# PC_PS2.net
KiCad netlist of a schematic drawn in Altium Designer
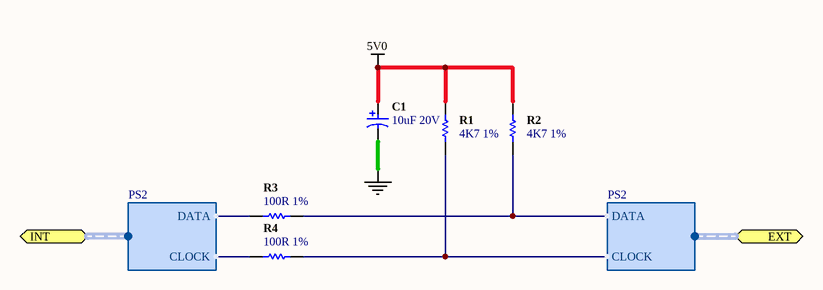
[diagram p0: PC_PS2.SchDoc]

(export (version "E")
  (design (tool "Eeschema 10.0.6"))
  (components
    (comp (ref "C1")
      (value "10uF 20V")
      (footprint "CAPC3528-STAR")
      (description "Capacitor, Tantalum, 10uF 10% 20V MCCT-B (3528)")
      (fields (field (name "TOLERANCE") "10 %"))
      (libsource (lib "altium-import") (part "root_0_CAP-P_"))
    )
    (comp (ref "R1")
      (value "4K7 1%")
      (footprint "RESC1005-STAR")
      (description "Resistor, 4K7 1% 0402 (1005)")
      (fields (field (name "TOLERANCE") "1 %"))
      (libsource (lib "altium-import") (part "root_0_RES_"))
    )
    (comp (ref "R2")
      (value "4K7 1%")
      (footprint "RESC1005-STAR")
      (description "Resistor, 4K7 1% 0402 (1005)")
      (fields (field (name "TOLERANCE") "1 %"))
      (libsource (lib "altium-import") (part "root_0_RES_"))
    )
    (comp (ref "R3")
      (value "100R 1%")
      (footprint "RESC1005-STAR")
      (description "Resistor, 100R 1% 0402 (1005)")
      (fields (field (name "TOLERANCE") "1 %"))
      (libsource (lib "altium-import") (part "root_1_RES_"))
    )
    (comp (ref "R4")
      (value "100R 1%")
      (footprint "RESC1005-STAR")
      (description "Resistor, 100R 1% 0402 (1005)")
      (fields (field (name "TOLERANCE") "1 %"))
      (libsource (lib "altium-import") (part "root_1_RES_"))
    )
  )
  (nets
    (net (code "3") (name "5V0") (class "Default")
      (node (ref "C1") (pin "1") (pinfunction "1_1") (pintype "passive"))
      (node (ref "R1") (pin "1") (pinfunction "1_1") (pintype "passive"))
      (node (ref "R2") (pin "1") (pinfunction "1_1") (pintype "passive"))
    )
    (net (code "4") (name "GND") (class "Default")
      (node (ref "C1") (pin "2") (pinfunction "2_2") (pintype "passive"))
    )
    (net (code "5") (name "Net-(R1-Pad2)") (class "Default")
      (node (ref "R1") (pin "2") (pinfunction "2_2") (pintype "passive"))
      (node (ref "R4") (pin "2") (pinfunction "2_2") (pintype "passive"))
    )
    (net (code "6") (name "Net-(R2-Pad2)") (class "Default")
      (node (ref "R2") (pin "2") (pinfunction "2_2") (pintype "passive"))
      (node (ref "R3") (pin "2") (pinfunction "2_2") (pintype "passive"))
    )
    (net (code "7") (name "unconnected-(R3-Pad1)") (class "Default")
      (node (ref "R3") (pin "1") (pinfunction "1_1") (pintype "passive"))
    )
    (net (code "8") (name "unconnected-(R4-Pad1)") (class "Default")
      (node (ref "R4") (pin "1") (pinfunction "1_1") (pintype "passive"))
    )
  )
)
